# Smart_Humidifier.net
KiCad netlist of a schematic drawn in Altium Designer
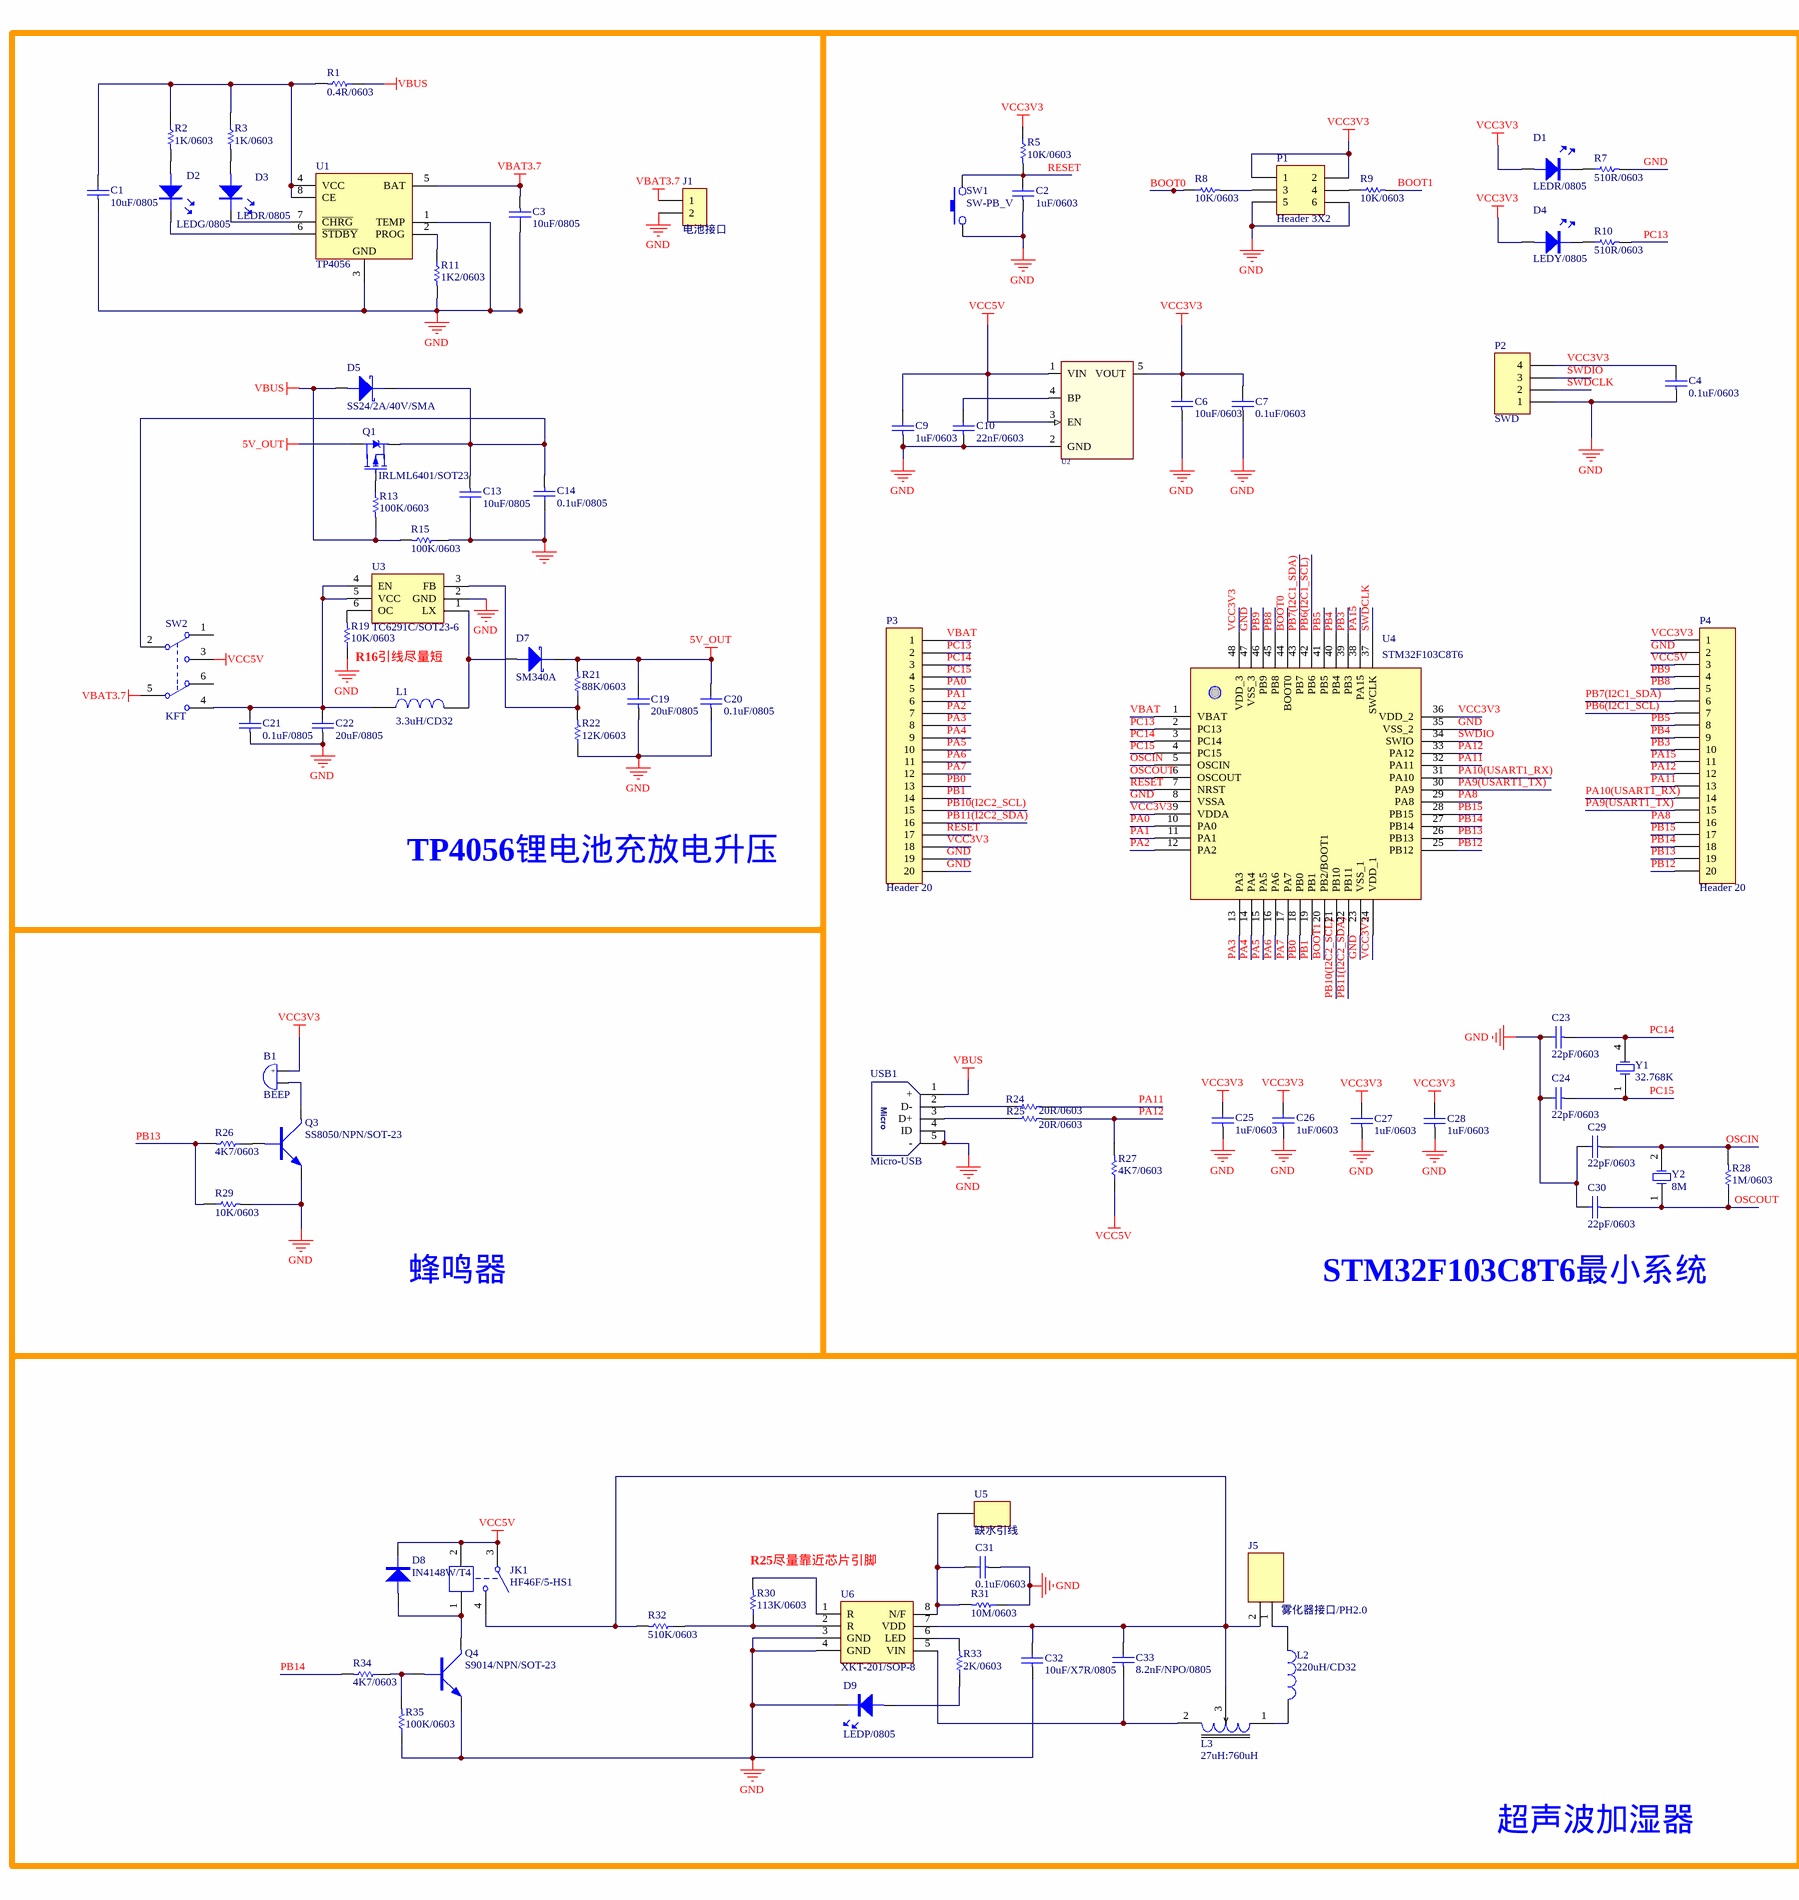
[diagram p0: Smart Humidifier.SchDoc, left]
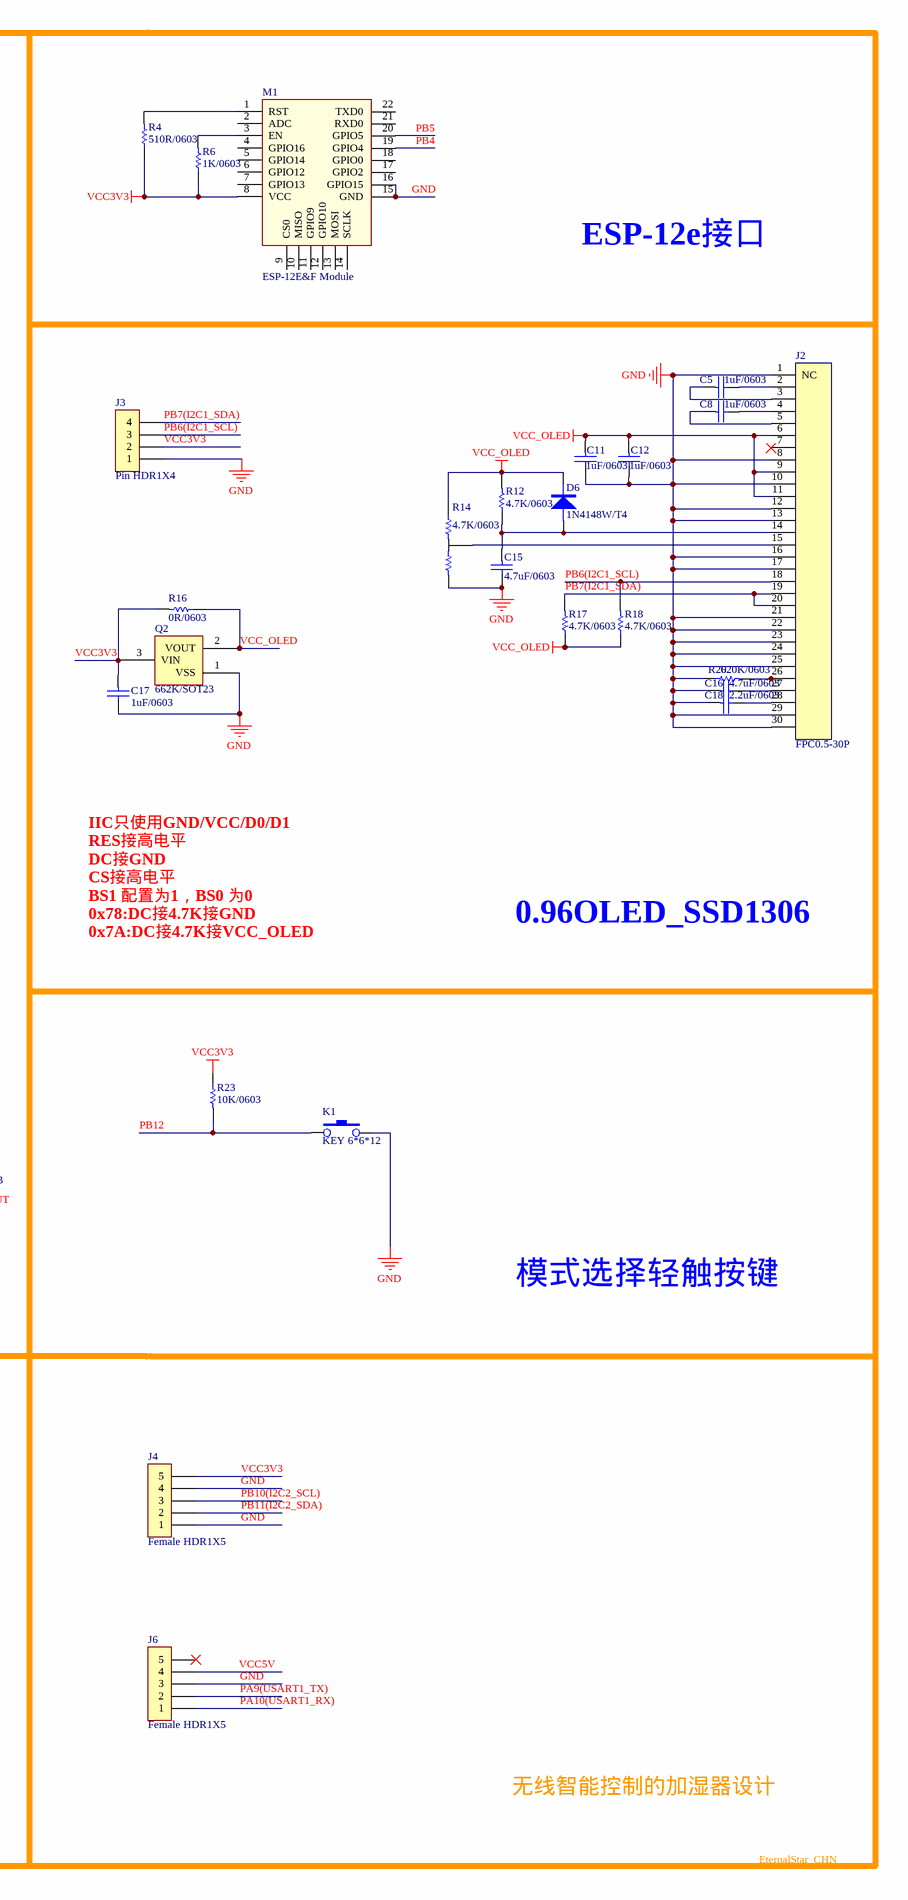
[diagram p1: Smart Humidifier.SchDoc, right]

(export (version "E")
  (design (tool "Eeschema 10.0.6"))
  (components
    (comp (ref "B1")
      (value "BEEP")
      (footprint "BEEP 5x9x5.5")
      (description "蜂鸣器")
      (libsource (lib "蜂鸣器") (part "BEEP"))
    )
    (comp (ref "C1")
      (value "10uF/0805")
      (footprint "0805C")
      (description "无极性电容")
      (libsource (lib "电容") (part "CAP"))
    )
    (comp (ref "C2")
      (value "1uF/0603")
      (footprint "0603C")
      (description "无极性电容")
      (libsource (lib "电容") (part "CAP"))
    )
    (comp (ref "C3")
      (value "10uF/0805")
      (footprint "0805C")
      (description "无极性电容")
      (libsource (lib "电容") (part "CAP"))
    )
    (comp (ref "C4")
      (value "0.1uF/0603")
      (footprint "0603C")
      (description "无极性电容")
      (libsource (lib "电容") (part "CAP"))
    )
    (comp (ref "C5")
      (value "1uF/0603")
      (footprint "0603C")
      (description "无极性电容")
      (libsource (lib "电容") (part "CAP"))
    )
    (comp (ref "C6")
      (value "10uF/0603")
      (footprint "0603C")
      (description "无极性电容")
      (libsource (lib "电容") (part "CAP"))
    )
    (comp (ref "C7")
      (value "0.1uF/0603")
      (footprint "0603C")
      (description "无极性电容")
      (libsource (lib "电容") (part "CAP"))
    )
    (comp (ref "C8")
      (value "1uF/0603")
      (footprint "0603C")
      (description "无极性电容")
      (libsource (lib "电容") (part "CAP"))
    )
    (comp (ref "C9")
      (value "1uF/0603")
      (footprint "0603C")
      (description "无极性电容")
      (libsource (lib "电容") (part "CAP"))
    )
    (comp (ref "C10")
      (value "22nF/0603")
      (footprint "0603C")
      (description "无极性电容")
      (libsource (lib "电容") (part "CAP"))
    )
    (comp (ref "C11")
      (value "1uF/0603")
      (footprint "0603C")
      (description "无极性电容")
      (libsource (lib "电容") (part "CAP"))
    )
    (comp (ref "C12")
      (value "1uF/0603")
      (footprint "0603C")
      (description "无极性电容")
      (libsource (lib "电容") (part "CAP"))
    )
    (comp (ref "C13")
      (value "10uF/0805")
      (footprint "0805C")
      (description "无极性电容")
      (libsource (lib "电容") (part "CAP"))
    )
    (comp (ref "C14")
      (value "0.1uF/0805")
      (footprint "0805C")
      (description "无极性电容")
      (libsource (lib "电容") (part "CAP"))
    )
    (comp (ref "C15")
      (value "4.7uF/0603")
      (footprint "0603C")
      (description "无极性电容")
      (libsource (lib "电容") (part "CAP"))
    )
    (comp (ref "C16")
      (value "4.7uF/0603")
      (footprint "0603C")
      (description "无极性电容")
      (libsource (lib "电容") (part "CAP"))
    )
    (comp (ref "C17")
      (value "1uF/0603")
      (footprint "0603C")
      (description "无极性电容")
      (libsource (lib "电容") (part "CAP"))
    )
    (comp (ref "C18")
      (value "2.2uF/0603")
      (footprint "0603C")
      (description "无极性电容")
      (libsource (lib "电容") (part "CAP"))
    )
    (comp (ref "C19")
      (value "20uF/0805")
      (footprint "0805C")
      (description "无极性电容")
      (libsource (lib "电容") (part "CAP"))
    )
    (comp (ref "C20")
      (value "0.1uF/0805")
      (footprint "0805C")
      (description "无极性电容")
      (libsource (lib "电容") (part "CAP"))
    )
    (comp (ref "C21")
      (value "0.1uF/0805")
      (footprint "0805C")
      (description "无极性电容")
      (libsource (lib "电容") (part "CAP"))
    )
    (comp (ref "C22")
      (value "20uF/0805")
      (footprint "0805C")
      (description "无极性电容")
      (libsource (lib "电容") (part "CAP"))
    )
    (comp (ref "C23")
      (value "22pF/0603")
      (footprint "0603C")
      (description "无极性电容")
      (libsource (lib "电容") (part "CAP"))
    )
    (comp (ref "C24")
      (value "22pF/0603")
      (footprint "0603C")
      (description "无极性电容")
      (libsource (lib "电容") (part "CAP"))
    )
    (comp (ref "C25")
      (value "1uF/0603")
      (footprint "0603C")
      (description "无极性电容")
      (libsource (lib "电容") (part "CAP"))
    )
    (comp (ref "C26")
      (value "1uF/0603")
      (footprint "0603C")
      (description "无极性电容")
      (libsource (lib "电容") (part "CAP"))
    )
    (comp (ref "C27")
      (value "1uF/0603")
      (footprint "0603C")
      (description "无极性电容")
      (libsource (lib "电容") (part "CAP"))
    )
    (comp (ref "C28")
      (value "1uF/0603")
      (footprint "0603C")
      (description "无极性电容")
      (libsource (lib "电容") (part "CAP"))
    )
    (comp (ref "C29")
      (value "22pF/0603")
      (footprint "0603C")
      (description "无极性电容")
      (libsource (lib "电容") (part "CAP"))
    )
    (comp (ref "C30")
      (value "22pF/0603")
      (footprint "0603C")
      (description "无极性电容")
      (libsource (lib "电容") (part "CAP"))
    )
    (comp (ref "C31")
      (value "0.1uF/0603")
      (footprint "0603C")
      (description "无极性电容")
      (libsource (lib "") (part "CAP_1"))
    )
    (comp (ref "C32")
      (value "10uF/X7R/0805")
      (footprint "0805C")
      (description "无极性电容")
      (libsource (lib "电容") (part "CAP"))
    )
    (comp (ref "C33")
      (value "8.2nF/NPO/0805")
      (footprint "0805C")
      (description "无极性电容")
      (libsource (lib "电容") (part "CAP"))
    )
    (comp (ref "D1") (value "LEDR/0805") (footprint "LED-0805R") (libsource (lib "LED") (part "LED")))
    (comp (ref "D2") (value "LEDG/0805") (footprint "LED-0805G") (libsource (lib "LED") (part "LED")))
    (comp (ref "D3") (value "LEDR/0805") (footprint "LED-0805R") (libsource (lib "LED") (part "LED")))
    (comp (ref "D4") (value "LEDY/0805") (footprint "LED-0805Y") (libsource (lib "LED") (part "LED")))
    (comp (ref "D5")
      (value "SS24/2A/40V/SMA")
      (footprint "SMA/DO-214AC")
      (description "肖特基二极管")
      (libsource (lib "二极管") (part "DIODE SCHOTTKY"))
    )
    (comp (ref "D6")
      (value "1N4148W/T4")
      (footprint "SOD-123")
      (description "普通二极管")
      (libsource (lib "二极管") (part "DIODE"))
    )
    (comp (ref "D7")
      (value "SM340A")
      (footprint "SMA/DO-214AC")
      (description "肖特基二极管")
      (libsource (lib "二极管") (part "DIODE SCHOTTKY"))
    )
    (comp (ref "D8")
      (value "IN4148W/T4")
      (footprint "SOD-123")
      (description "普通二极管")
      (libsource (lib "二极管") (part "DIODE"))
    )
    (comp (ref "D9") (value "LEDP/0805") (footprint "LED-0805Y") (libsource (lib "LED") (part "LED")))
    (comp (ref "J1")
      (value "电池接口")
      (footprint "Fe-HDR1X2/2.54-S")
      (libsource (lib "排母") (part "Female HDR1X2"))
    )
    (comp (ref "J2")
      (value "FPC0.5-30P")
      (footprint "FPC0.5-30P")
      (description "贴片")
      (libsource (lib "FPC") (part "FPC0.5-30P"))
    )
    (comp (ref "J3")
      (value "Pin HDR1X4")
      (footprint "Pin HDR1X4/2.54mm-S")
      (libsource (lib "排针") (part "Pin HDR1X4"))
    )
    (comp (ref "J4")
      (value "Female HDR1X5")
      (footprint "Fe-HDR1X5/2.54-S")
      (libsource (lib "排母") (part "Female HDR1X5"))
    )
    (comp (ref "J5") (value "雾化器接口/PH2.0") (footprint "PH2.0-2P") (libsource (lib "PH") (part "PH2.0-2P")))
    (comp (ref "J6")
      (value "Female HDR1X5")
      (footprint "Fe-HDR1X5/2.54-S")
      (libsource (lib "排母") (part "Female HDR1X5"))
    )
    (comp (ref "JK1")
      (value "HF46F/5-HS1")
      (footprint "HF46-xx-HS1")
      (description "5V一组常开")
      (libsource (lib "继电器") (part "HF46F/5-HS1"))
    )
    (comp (ref "K1") (value "KEY 6*6*12") (footprint "DIP-6X6X12_C") (libsource (lib "轻触开关") (part "KEY")))
    (comp (ref "L1")
      (value "3.3uH/CD32")
      (footprint "CD32")
      (description "INDUCTOR")
      (libsource (lib "电感") (part "INDUCTOR"))
    )
    (comp (ref "L2")
      (value "220uH/CD32")
      (footprint "CD32")
      (description "INDUCTOR")
      (libsource (lib "Smart Humidifier") (part "INDUCTOR"))
    )
    (comp (ref "L3")
      (value "27uH:760uH")
      (footprint "INDUCTOR Tripod")
      (description "三脚工字形电感线圈直插式")
      (libsource (lib "Smart Humidifier") (part "INDUCTOR Tripod"))
    )
    (comp (ref "M1")
      (value "ESP-12E&F Module")
      (footprint "ESP-12E&F Module")
      (libsource (lib "ESP模块") (part "ESP-12E&F Module"))
    )
    (comp (ref "P1")
      (value "Header 3X2")
      (footprint "HDR-3X2")
      (description "Header, 3-Pin, Dual row")
      (libsource (lib "STM32F103C8T6") (part "Header 3X2"))
    )
    (comp (ref "P2")
      (value "SWD")
      (footprint "HDR-1X4_H")
      (description "Header, 4-Pin")
      (libsource (lib "STM32F103C8T6") (part "Header 4"))
    )
    (comp (ref "P3")
      (value "Header 20")
      (footprint "HDR1X20")
      (description "Header, 20-Pin")
      (libsource (lib "STM32F103C8T6") (part "Header 20"))
    )
    (comp (ref "P4")
      (value "Header 20")
      (footprint "HDR1X20")
      (description "Header, 20-Pin")
      (libsource (lib "") (part "Header 20_1"))
    )
    (comp (ref "Q1")
      (value "IRLML6401/SOT23")
      (footprint "SOT23")
      (description "P沟道场效应管")
      (libsource (lib "MOS管") (part "P-MOS"))
    )
    (comp (ref "Q2")
      (value "662K/SOT23")
      (footprint "SOT23")
      (description "SOT23封装LDO")
      (libsource (lib "电源芯片") (part "LDO_SOT23"))
    )
    (comp (ref "Q3")
      (value "SS8050/NPN/SOT-23")
      (footprint "SOT-23")
      (description "NPN三极管")
      (libsource (lib "三极管") (part "NPN"))
    )
    (comp (ref "Q4")
      (value "S9014/NPN/SOT-23")
      (footprint "SOT-23")
      (description "NPN三极管")
      (libsource (lib "三极管") (part "NPN"))
    )
    (comp (ref "R1") (value "0.4R/0603") (footprint "0603R") (libsource (lib "电阻") (part "RES")))
    (comp (ref "R2") (value "1K/0603") (footprint "0603R") (libsource (lib "电阻") (part "RES")))
    (comp (ref "R3") (value "1K/0603") (footprint "0603R") (libsource (lib "电阻") (part "RES")))
    (comp (ref "R4") (value "510R/0603") (footprint "0603R") (libsource (lib "电阻") (part "RES")))
    (comp (ref "R5") (value "10K/0603") (footprint "0603R") (libsource (lib "电阻") (part "RES")))
    (comp (ref "R6") (value "1K/0603") (footprint "0603R") (libsource (lib "电阻") (part "RES")))
    (comp (ref "R7") (value "510R/0603") (footprint "0603R") (libsource (lib "电阻") (part "RES")))
    (comp (ref "R8") (value "10K/0603") (footprint "0603R") (libsource (lib "电阻") (part "RES")))
    (comp (ref "R9") (value "10K/0603") (footprint "0603R") (libsource (lib "电阻") (part "RES")))
    (comp (ref "R10") (value "510R/0603") (footprint "0603R") (libsource (lib "电阻") (part "RES")))
    (comp (ref "R11") (value "1K2/0603") (footprint "0603R") (libsource (lib "电阻") (part "RES")))
    (comp (ref "R12") (value "4.7K/0603") (footprint "0603R") (libsource (lib "电阻") (part "RES")))
    (comp (ref "R13") (value "100K/0603") (footprint "0603R") (libsource (lib "电阻") (part "RES")))
    (comp (ref "R14") (value "4.7K/0603") (footprint "SW_0603R") (libsource (lib "电阻") (part "RES_SW")))
    (comp (ref "R15") (value "100K/0603") (footprint "0603R") (libsource (lib "电阻") (part "RES")))
    (comp (ref "R16") (value "0R/0603") (footprint "0603R") (libsource (lib "电阻") (part "RES")))
    (comp (ref "R17") (value "4.7K/0603") (footprint "0603R") (libsource (lib "电阻") (part "RES")))
    (comp (ref "R18") (value "4.7K/0603") (footprint "0603R") (libsource (lib "电阻") (part "RES")))
    (comp (ref "R19") (value "10K/0603") (footprint "0603R") (libsource (lib "电阻") (part "RES")))
    (comp (ref "R20") (value "620K/0603") (footprint "0603R") (libsource (lib "电阻") (part "RES")))
    (comp (ref "R21") (value "88K/0603") (footprint "0603R") (libsource (lib "电阻") (part "RES")))
    (comp (ref "R22") (value "12K/0603") (footprint "0603R") (libsource (lib "电阻") (part "RES")))
    (comp (ref "R23") (value "10K/0603") (footprint "0603R") (libsource (lib "电阻") (part "RES")))
    (comp (ref "R24") (value "20R/0603") (footprint "0603R") (libsource (lib "电阻") (part "RES")))
    (comp (ref "R25") (value "20R/0603") (footprint "0603R") (libsource (lib "电阻") (part "RES")))
    (comp (ref "R26") (value "4K7/0603") (footprint "0603R") (libsource (lib "电阻") (part "RES")))
    (comp (ref "R27") (value "4K7/0603") (footprint "0603R") (libsource (lib "电阻") (part "RES")))
    (comp (ref "R28") (value "1M/0603") (footprint "0603R") (libsource (lib "电阻") (part "RES")))
    (comp (ref "R29") (value "10K/0603") (footprint "0603R") (libsource (lib "电阻") (part "RES")))
    (comp (ref "R30") (value "113K/0603") (footprint "0603R") (libsource (lib "电阻") (part "RES")))
    (comp (ref "R31") (value "10M/0603") (footprint "0603R") (libsource (lib "电阻") (part "RES")))
    (comp (ref "R32") (value "510K/0603") (footprint "0603R") (libsource (lib "电阻") (part "RES")))
    (comp (ref "R33") (value "2K/0603") (footprint "0603R") (libsource (lib "电阻") (part "RES")))
    (comp (ref "R34") (value "4K7/0603") (footprint "0603R") (libsource (lib "电阻") (part "RES")))
    (comp (ref "R35") (value "100K/0603") (footprint "0603R") (libsource (lib "电阻") (part "RES")))
    (comp (ref "SW1")
      (value "SW-PB_V")
      (footprint "TSW SMD-3*6*2.5")
      (description "SWITCH")
      (libsource (lib "STM32F103C8T6") (part "SW-PB_V"))
    )
    (comp (ref "SW2")
      (value "KFT")
      (footprint "KFT DIP-7X7")
      (description "Self-locking Switch")
      (libsource (lib "Smart Humidifier") (part "KFT_7X7-DIP"))
    )
    (comp (ref "U1") (value "TP4056") (footprint "SOP8") (libsource (lib "电源芯片") (part "TP4056")))
    (comp (ref "U2")
      (value "RT9193")
      (footprint "SOT23-5L")
      (fields (field (name "ICA_PARTNUM") "$$2191094$$RT9193-15CU5") (field (name "PART NUMBER") "TMP-13"))
      (libsource (lib "STM32F103C8T6") (part "RT9193X_5P"))
    )
    (comp (ref "U3")
      (value "TC6291C/SOT23-6")
      (footprint "SOT23-6")
      (description "DC-DC升压IC")
      (libsource (lib "Li_Test") (part "TC6291C"))
    )
    (comp (ref "U4")
      (value "STM32F103C8T6")
      (footprint "TQFP48 7x7_L")
      (libsource (lib "STM32F103C8T6") (part "STM32F103C8T6"))
    )
    (comp (ref "U5") (value "缺水引线") (footprint "通孔焊盘") (libsource (lib "Smart Humidifier") (part "过孔焊盘")))
    (comp (ref "U6")
      (value "XKT-201/SOP-8")
      (footprint "SOP8")
      (description "5V加湿器驱动芯片")
      (libsource (lib "Smart Humidifier") (part "XKT-201"))
    )
    (comp (ref "USB1")
      (value "Micro-USB")
      (footprint "USB-micro_B")
      (libsource (lib "USB") (part "Micro-USB"))
    )
    (comp (ref "Y1")
      (value "32.768K")
      (footprint "MC-306")
      (description "Crystal Oscillator")
      (libsource (lib "STM32F103C8T6") (part "XTAL"))
    )
    (comp (ref "Y2")
      (value "8M")
      (footprint "XTAL-49S DIP")
      (description "Crystal Oscillator")
      (libsource (lib "") (part "XTAL_1"))
    )
  )
  (nets
    (net (code "1") (name "/BOOT0") (class "Default")
      (node (ref "R8") (pin "1") (pinfunction "1_1") (pintype "passive"))
      (node (ref "U4") (pin "44") (pinfunction "BOOT0_44") (pintype "passive"))
    )
    (net (code "2") (name "/BOOT1") (class "Default")
      (node (ref "R9") (pin "2") (pinfunction "2_2") (pintype "passive"))
      (node (ref "U4") (pin "20") (pinfunction "PB2/BOOT1_20") (pintype "passive"))
    )
    (net (code "3") (name "/OSCIN") (class "Default")
      (node (ref "C29") (pin "1") (pinfunction "1_1") (pintype "passive"))
      (node (ref "R28") (pin "2") (pinfunction "2_2") (pintype "passive"))
      (node (ref "U4") (pin "5") (pinfunction "OSCIN_5") (pintype "passive"))
      (node (ref "Y2") (pin "2") (pinfunction "OSC2_2") (pintype "passive"))
    )
    (net (code "4") (name "/OSCOUT") (class "Default")
      (node (ref "C30") (pin "1") (pinfunction "1_1") (pintype "passive"))
      (node (ref "R28") (pin "1") (pinfunction "1_1") (pintype "passive"))
      (node (ref "U4") (pin "6") (pinfunction "OSCOUT_6") (pintype "passive"))
      (node (ref "Y2") (pin "1") (pinfunction "OSC1_1") (pintype "passive"))
    )
    (net (code "5") (name "/PA0") (class "Default")
      (node (ref "P3") (pin "5") (pinfunction "5_5") (pintype "passive"))
      (node (ref "U4") (pin "10") (pinfunction "PA0_10") (pintype "passive"))
    )
    (net (code "6") (name "/PA1") (class "Default")
      (node (ref "P3") (pin "6") (pinfunction "6_6") (pintype "passive"))
      (node (ref "U4") (pin "11") (pinfunction "PA1_11") (pintype "passive"))
    )
    (net (code "7") (name "/PA2") (class "Default")
      (node (ref "P3") (pin "7") (pinfunction "7_7") (pintype "passive"))
      (node (ref "U4") (pin "12") (pinfunction "PA2_12") (pintype "passive"))
    )
    (net (code "8") (name "/PA3") (class "Default")
      (node (ref "P3") (pin "8") (pinfunction "8_8") (pintype "passive"))
      (node (ref "U4") (pin "13") (pinfunction "PA3_13") (pintype "passive"))
    )
    (net (code "9") (name "/PA4") (class "Default")
      (node (ref "P3") (pin "9") (pinfunction "9_9") (pintype "passive"))
      (node (ref "U4") (pin "14") (pinfunction "PA4_14") (pintype "passive"))
    )
    (net (code "10") (name "/PA5") (class "Default")
      (node (ref "P3") (pin "10") (pinfunction "10_10") (pintype "passive"))
      (node (ref "U4") (pin "15") (pinfunction "PA5_15") (pintype "passive"))
    )
    (net (code "11") (name "/PA6") (class "Default")
      (node (ref "P3") (pin "11") (pinfunction "11_11") (pintype "passive"))
      (node (ref "U4") (pin "16") (pinfunction "PA6_16") (pintype "passive"))
    )
    (net (code "12") (name "/PA7") (class "Default")
      (node (ref "P3") (pin "12") (pinfunction "12_12") (pintype "passive"))
      (node (ref "U4") (pin "17") (pinfunction "PA7_17") (pintype "passive"))
    )
    (net (code "13") (name "/PA8") (class "Default")
      (node (ref "P4") (pin "16") (pinfunction "16_16") (pintype "passive"))
      (node (ref "U4") (pin "29") (pinfunction "PA8_29") (pintype "passive"))
    )
    (net (code "14") (name "/PA9(USART1_TX)") (class "Default")
      (node (ref "J6") (pin "2") (pinfunction "2_2") (pintype "passive"))
      (node (ref "P4") (pin "15") (pinfunction "15_15") (pintype "passive"))
      (node (ref "U4") (pin "30") (pinfunction "PA9_30") (pintype "passive"))
    )
    (net (code "15") (name "/PA10(USART1_RX)") (class "Default")
      (node (ref "J6") (pin "1") (pinfunction "1_1") (pintype "passive"))
      (node (ref "P4") (pin "14") (pinfunction "14_14") (pintype "passive"))
      (node (ref "U4") (pin "31") (pinfunction "PA10_31") (pintype "passive"))
    )
    (net (code "16") (name "/PA11") (class "Default")
      (node (ref "P4") (pin "13") (pinfunction "13_13") (pintype "passive"))
      (node (ref "R24") (pin "2") (pinfunction "2_2") (pintype "passive"))
      (node (ref "U4") (pin "32") (pinfunction "PA11_32") (pintype "passive"))
    )
    (net (code "17") (name "/PA12") (class "Default")
      (node (ref "P4") (pin "12") (pinfunction "12_12") (pintype "passive"))
      (node (ref "R25") (pin "2") (pinfunction "2_2") (pintype "passive"))
      (node (ref "R27") (pin "2") (pinfunction "2_2") (pintype "passive"))
      (node (ref "U4") (pin "33") (pinfunction "PA12_33") (pintype "passive"))
    )
    (net (code "18") (name "/PA15") (class "Default")
      (node (ref "P4") (pin "11") (pinfunction "11_11") (pintype "passive"))
      (node (ref "U4") (pin "38") (pinfunction "PA15_38") (pintype "passive"))
    )
    (net (code "19") (name "/PB0") (class "Default")
      (node (ref "P3") (pin "13") (pinfunction "13_13") (pintype "passive"))
      (node (ref "U4") (pin "18") (pinfunction "PB0_18") (pintype "passive"))
    )
    (net (code "20") (name "/PB1") (class "Default")
      (node (ref "P3") (pin "14") (pinfunction "14_14") (pintype "passive"))
      (node (ref "U4") (pin "19") (pinfunction "PB1_19") (pintype "passive"))
    )
    (net (code "21") (name "/PB3") (class "Default")
      (node (ref "P4") (pin "10") (pinfunction "10_10") (pintype "passive"))
      (node (ref "U4") (pin "39") (pinfunction "PB3_39") (pintype "passive"))
    )
    (net (code "22") (name "/PB4") (class "Default")
      (node (ref "M1") (pin "19") (pinfunction "GPIO4_19") (pintype "passive"))
      (node (ref "P4") (pin "9") (pinfunction "9_9") (pintype "passive"))
      (node (ref "U4") (pin "40") (pinfunction "PB4_40") (pintype "passive"))
    )
    (net (code "23") (name "/PB5") (class "Default")
      (node (ref "M1") (pin "20") (pinfunction "GPIO5_20") (pintype "passive"))
      (node (ref "P4") (pin "8") (pinfunction "8_8") (pintype "passive"))
      (node (ref "U4") (pin "41") (pinfunction "PB5_41") (pintype "passive"))
    )
    (net (code "24") (name "/PB6(I2C1_SCL)") (class "Default")
      (node (ref "J2") (pin "18") (pinfunction "D0_18") (pintype "passive"))
      (node (ref "J3") (pin "3") (pinfunction "3_3") (pintype "passive"))
      (node (ref "P4") (pin "7") (pinfunction "7_7") (pintype "passive"))
      (node (ref "R18") (pin "2") (pinfunction "2_2") (pintype "passive"))
      (node (ref "U4") (pin "42") (pinfunction "PB6_42") (pintype "passive"))
    )
    (net (code "25") (name "/PB7(I2C1_SDA)") (class "Default")
      (node (ref "J2") (pin "19") (pinfunction "D1_19") (pintype "passive"))
      (node (ref "J2") (pin "20") (pinfunction "D2_20") (pintype "passive"))
      (node (ref "J3") (pin "4") (pinfunction "4_4") (pintype "passive"))
      (node (ref "P4") (pin "6") (pinfunction "6_6") (pintype "passive"))
      (node (ref "R17") (pin "2") (pinfunction "2_2") (pintype "passive"))
      (node (ref "U4") (pin "43") (pinfunction "PB7_43") (pintype "passive"))
    )
    (net (code "26") (name "/PB8") (class "Default")
      (node (ref "P4") (pin "5") (pinfunction "5_5") (pintype "passive"))
      (node (ref "U4") (pin "45") (pinfunction "PB8_45") (pintype "passive"))
    )
    (net (code "27") (name "/PB9") (class "Default")
      (node (ref "P4") (pin "4") (pinfunction "4_4") (pintype "passive"))
      (node (ref "U4") (pin "46") (pinfunction "PB9_46") (pintype "passive"))
    )
    (net (code "28") (name "/PB10(I2C2_SCL)") (class "Default")
      (node (ref "J4") (pin "3") (pinfunction "3_3") (pintype "passive"))
      (node (ref "P3") (pin "15") (pinfunction "15_15") (pintype "passive"))
      (node (ref "U4") (pin "21") (pinfunction "PB10_21") (pintype "passive"))
    )
    (net (code "29") (name "/PB11(I2C2_SDA)") (class "Default")
      (node (ref "J4") (pin "2") (pinfunction "2_2") (pintype "passive"))
      (node (ref "P3") (pin "16") (pinfunction "16_16") (pintype "passive"))
      (node (ref "U4") (pin "22") (pinfunction "PB11_22") (pintype "passive"))
    )
    (net (code "30") (name "/PB12") (class "Default")
      (node (ref "K1") (pin "1") (pinfunction "1_1") (pintype "passive"))
      (node (ref "P4") (pin "20") (pinfunction "20_20") (pintype "passive"))
      (node (ref "R23") (pin "2") (pinfunction "2_2") (pintype "passive"))
      (node (ref "U4") (pin "25") (pinfunction "PB12_25") (pintype "passive"))
    )
    (net (code "31") (name "/PB13") (class "Default")
      (node (ref "P4") (pin "19") (pinfunction "19_19") (pintype "passive"))
      (node (ref "R26") (pin "2") (pinfunction "2_2") (pintype "passive"))
      (node (ref "R29") (pin "1") (pinfunction "1_1") (pintype "passive"))
      (node (ref "U4") (pin "26") (pinfunction "PB13_26") (pintype "passive"))
    )
    (net (code "32") (name "/PB14") (class "Default")
      (node (ref "P4") (pin "18") (pinfunction "18_18") (pintype "passive"))
      (node (ref "R34") (pin "2") (pinfunction "2_2") (pintype "passive"))
      (node (ref "U4") (pin "27") (pinfunction "PB14_27") (pintype "passive"))
    )
    (net (code "33") (name "/PB15") (class "Default")
      (node (ref "P4") (pin "17") (pinfunction "17_17") (pintype "passive"))
      (node (ref "U4") (pin "28") (pinfunction "PB15_28") (pintype "passive"))
    )
    (net (code "34") (name "/PC13") (class "Default")
      (node (ref "P3") (pin "2") (pinfunction "2_2") (pintype "passive"))
      (node (ref "R10") (pin "2") (pinfunction "2_2") (pintype "passive"))
      (node (ref "U4") (pin "2") (pinfunction "PC13_2") (pintype "passive"))
    )
    (net (code "35") (name "/PC14") (class "Default")
      (node (ref "C23") (pin "1") (pinfunction "1_1") (pintype "passive"))
      (node (ref "P3") (pin "3") (pinfunction "3_3") (pintype "passive"))
      (node (ref "U4") (pin "3") (pinfunction "PC14_3") (pintype "passive"))
      (node (ref "Y1") (pin "4") (pinfunction "OSC2_4") (pintype "passive"))
    )
    (net (code "36") (name "/PC15") (class "Default")
      (node (ref "C24") (pin "1") (pinfunction "1_1") (pintype "passive"))
      (node (ref "P3") (pin "4") (pinfunction "4_4") (pintype "passive"))
      (node (ref "U4") (pin "4") (pinfunction "PC15_4") (pintype "passive"))
      (node (ref "Y1") (pin "1") (pinfunction "OSC1_1") (pintype "passive"))
    )
    (net (code "37") (name "/RESET") (class "Default")
      (node (ref "C2") (pin "2") (pinfunction "2_2") (pintype "passive"))
      (node (ref "P3") (pin "17") (pinfunction "17_17") (pintype "passive"))
      (node (ref "R5") (pin "2") (pinfunction "2_2") (pintype "passive"))
      (node (ref "SW1") (pin "2") (pinfunction "2_2") (pintype "passive"))
      (node (ref "U4") (pin "7") (pinfunction "NRST_7") (pintype "passive"))
    )
    (net (code "38") (name "/SWDCLK") (class "Default")
      (node (ref "P2") (pin "2") (pinfunction "2_2") (pintype "passive"))
      (node (ref "U4") (pin "37") (pinfunction "SWCLK_37") (pintype "passive"))
    )
    (net (code "39") (name "/SWDIO") (class "Default")
      (node (ref "P2") (pin "3") (pinfunction "3_3") (pintype "passive"))
      (node (ref "U4") (pin "34") (pinfunction "SWIO_34") (pintype "passive"))
    )
    (net (code "40") (name "/VBAT") (class "Default")
      (node (ref "P3") (pin "1") (pinfunction "1_1") (pintype "passive"))
      (node (ref "U4") (pin "1") (pinfunction "VBAT_1") (pintype "passive"))
    )
    (net (code "41") (name "5V_OUT") (class "Default")
      (node (ref "C19") (pin "2") (pinfunction "2_2") (pintype "passive"))
      (node (ref "C20") (pin "2") (pinfunction "2_2") (pintype "passive"))
      (node (ref "D7") (pin "K") (pinfunction "K_K") (pintype "passive"))
      (node (ref "Q1") (pin "D") (pinfunction "D_D") (pintype "passive"))
      (node (ref "R21") (pin "2") (pinfunction "2_2") (pintype "passive"))
    )
    (net (code "42") (name "GND") (class "Default")
      (node (ref "C1") (pin "1") (pinfunction "1_1") (pintype "passive"))
      (node (ref "C10") (pin "1") (pinfunction "1_1") (pintype "passive"))
      (node (ref "C11") (pin "2") (pinfunction "2_2") (pintype "passive"))
      (node (ref "C12") (pin "2") (pinfunction "2_2") (pintype "passive"))
      (node (ref "C13") (pin "2") (pinfunction "2_2") (pintype "passive"))
      (node (ref "C14") (pin "2") (pinfunction "2_2") (pintype "passive"))
      (node (ref "C15") (pin "2") (pinfunction "2_2") (pintype "passive"))
      (node (ref "C16") (pin "1") (pinfunction "1_1") (pintype "passive"))
      (node (ref "C17") (pin "2") (pinfunction "2_2") (pintype "passive"))
      (node (ref "C18") (pin "1") (pinfunction "1_1") (pintype "passive"))
      (node (ref "C19") (pin "1") (pinfunction "1_1") (pintype "passive"))
      (node (ref "C2") (pin "1") (pinfunction "1_1") (pintype "passive"))
      (node (ref "C20") (pin "1") (pinfunction "1_1") (pintype "passive"))
      (node (ref "C21") (pin "1") (pinfunction "1_1") (pintype "passive"))
      (node (ref "C22") (pin "1") (pinfunction "1_1") (pintype "passive"))
      (node (ref "C23") (pin "2") (pinfunction "2_2") (pintype "passive"))
      (node (ref "C24") (pin "2") (pinfunction "2_2") (pintype "passive"))
      (node (ref "C25") (pin "1") (pinfunction "1_1") (pintype "passive"))
      (node (ref "C26") (pin "1") (pinfunction "1_1") (pintype "passive"))
      (node (ref "C27") (pin "1") (pinfunction "1_1") (pintype "passive"))
      (node (ref "C28") (pin "1") (pinfunction "1_1") (pintype "passive"))
      (node (ref "C29") (pin "2") (pinfunction "2_2") (pintype "passive"))
      (node (ref "C3") (pin "2") (pinfunction "2_2") (pintype "passive"))
      (node (ref "C30") (pin "2") (pinfunction "2_2") (pintype "passive"))
      (node (ref "C31") (pin "2") (pinfunction "2_2") (pintype "passive"))
      (node (ref "C32") (pin "1") (pinfunction "1_1") (pintype "passive"))
      (node (ref "C4") (pin "1") (pinfunction "1_1") (pintype "passive"))
      (node (ref "C6") (pin "1") (pinfunction "1_1") (pintype "passive"))
      (node (ref "C7") (pin "1") (pinfunction "1_1") (pintype "passive"))
      (node (ref "C9") (pin "1") (pinfunction "1_1") (pintype "passive"))
      (node (ref "D9") (pin "K") (pinfunction "K_K") (pintype "passive"))
      (node (ref "J1") (pin "2") (pinfunction "2_2") (pintype "passive"))
      (node (ref "J2") (pin "1") (pinfunction "NC_1") (pintype "passive"))
      (node (ref "J2") (pin "10") (pinfunction "BS0_10") (pintype "passive"))
      (node (ref "J2") (pin "12") (pinfunction "NC_12") (pintype "passive"))
      (node (ref "J2") (pin "13") (pinfunction "CS_13") (pintype "passive"))
      (node (ref "J2") (pin "16") (pinfunction "E/RD_16") (pintype "passive"))
      (node (ref "J2") (pin "17") (pinfunction "R/W_17") (pintype "passive"))
      (node (ref "J2") (pin "21") (pinfunction "D3_21") (pintype "passive"))
      (node (ref "J2") (pin "22") (pinfunction "D4_22") (pintype "passive"))
      (node (ref "J2") (pin "23") (pinfunction "D5_23") (pintype "passive"))
      (node (ref "J2") (pin "24") (pinfunction "D6_24") (pintype "passive"))
      (node (ref "J2") (pin "25") (pinfunction "D7_25") (pintype "passive"))
      (node (ref "J2") (pin "29") (pinfunction "VLSS_29") (pintype "passive"))
      (node (ref "J2") (pin "30") (pinfunction "NC_30") (pintype "passive"))
      (node (ref "J2") (pin "8") (pinfunction "VSS_8") (pintype "passive"))
      (node (ref "J3") (pin "1") (pinfunction "1_1") (pintype "passive"))
      (node (ref "J4") (pin "1") (pinfunction "1_1") (pintype "passive"))
      (node (ref "J4") (pin "4") (pinfunction "4_4") (pintype "passive"))
      (node (ref "J6") (pin "3") (pinfunction "3_3") (pintype "passive"))
      (node (ref "K1") (pin "3") (pinfunction "3_3") (pintype "passive"))
      (node (ref "M1") (pin "15") (pinfunction "GND_15") (pintype "passive"))
      (node (ref "M1") (pin "16") (pinfunction "GPIO15_16") (pintype "passive"))
      (node (ref "P1") (pin "5") (pinfunction "5_5") (pintype "passive"))
      (node (ref "P1") (pin "6") (pinfunction "6_6") (pintype "passive"))
      (node (ref "P2") (pin "1") (pinfunction "1_1") (pintype "passive"))
      (node (ref "P3") (pin "19") (pinfunction "19_19") (pintype "passive"))
      (node (ref "P3") (pin "20") (pinfunction "20_20") (pintype "passive"))
      (node (ref "P4") (pin "2") (pinfunction "2_2") (pintype "passive"))
      (node (ref "Q2") (pin "1") (pinfunction "VSS_1") (pintype "passive"))
      (node (ref "Q3") (pin "E") (pinfunction "E_E") (pintype "passive"))
      (node (ref "Q4") (pin "E") (pinfunction "E_E") (pintype "passive"))
      (node (ref "R11") (pin "2") (pinfunction "2_2") (pintype "passive"))
      (node (ref "R14") (pin "3") (pinfunction "3_3") (pintype "passive"))
      (node (ref "R15") (pin "1") (pinfunction "1_1") (pintype "passive"))
      (node (ref "R19") (pin "1") (pinfunction "1_1") (pintype "passive"))
      (node (ref "R20") (pin "1") (pinfunction "1_1") (pintype "passive"))
      (node (ref "R22") (pin "1") (pinfunction "1_1") (pintype "passive"))
      (node (ref "R29") (pin "2") (pinfunction "2_2") (pintype "passive"))
      (node (ref "R31") (pin "1") (pinfunction "1_1") (pintype "passive"))
      (node (ref "R35") (pin "1") (pinfunction "1_1") (pintype "passive"))
      (node (ref "R7") (pin "2") (pinfunction "2_2") (pintype "passive"))
      (node (ref "SW1") (pin "1") (pinfunction "1_1") (pintype "passive"))
      (node (ref "U1") (pin "1") (pinfunction "TEMP_1") (pintype "passive"))
      (node (ref "U1") (pin "3") (pinfunction "GND_3") (pintype "passive"))
      (node (ref "U2") (pin "2") (pinfunction "GND_2") (pintype "power_in"))
      (node (ref "U3") (pin "2") (pinfunction "GND_2") (pintype "passive"))
      (node (ref "U4") (pin "23") (pinfunction "VSS_1_23") (pintype "passive"))
      (node (ref "U4") (pin "35") (pinfunction "VSS_2_35") (pintype "passive"))
      (node (ref "U4") (pin "47") (pinfunction "VSS_3_47") (pintype "passive"))
      (node (ref "U4") (pin "8") (pinfunction "VSSA_8") (pintype "passive"))
      (node (ref "U6") (pin "3") (pinfunction "GND_3") (pintype "passive"))
      (node (ref "U6") (pin "4") (pinfunction "GND_4") (pintype "passive"))
      (node (ref "USB1") (pin "4") (pinfunction "ID_4") (pintype "passive"))
      (node (ref "USB1") (pin "5") (pinfunction "-_5") (pintype "passive"))
    )
    (net (code "43") (name "Net-(B1-Pad2)") (class "Default")
      (node (ref "B1") (pin "2") (pinfunction "2_2") (pintype "passive"))
      (node (ref "Q3") (pin "C") (pinfunction "C_C") (pintype "passive"))
    )
    (net (code "44") (name "Net-(C13-Pad1)") (class "Default")
      (node (ref "C13") (pin "1") (pinfunction "1_1") (pintype "passive"))
      (node (ref "C14") (pin "1") (pinfunction "1_1") (pintype "passive"))
      (node (ref "D5") (pin "K") (pinfunction "K_K") (pintype "passive"))
      (node (ref "Q1") (pin "S") (pinfunction "S_S") (pintype "passive"))
      (node (ref "SW2") (pin "2") (pinfunction "COM2_2") (pintype "passive"))
    )
    (net (code "45") (name "Net-(D1-PadK)") (class "Default")
      (node (ref "D1") (pin "K") (pinfunction "K_K") (pintype "passive"))
      (node (ref "R7") (pin "1") (pinfunction "1_1") (pintype "passive"))
    )
    (net (code "46") (name "Net-(D2-PadA)") (class "Default")
      (node (ref "D2") (pin "A") (pinfunction "A_A") (pintype "passive"))
      (node (ref "R2") (pin "2") (pinfunction "2_2") (pintype "passive"))
    )
    (net (code "47") (name "Net-(D3-PadA)") (class "Default")
      (node (ref "D3") (pin "A") (pinfunction "A_A") (pintype "passive"))
      (node (ref "R3") (pin "2") (pinfunction "2_2") (pintype "passive"))
    )
    (net (code "48") (name "Net-(D4-PadK)") (class "Default")
      (node (ref "D4") (pin "K") (pinfunction "K_K") (pintype "passive"))
      (node (ref "R10") (pin "1") (pinfunction "1_1") (pintype "passive"))
    )
    (net (code "49") (name "Net-(D8-PadA)") (class "Default")
      (node (ref "D8") (pin "A") (pinfunction "A_A") (pintype "passive"))
      (node (ref "JK1") (pin "1") (pinfunction "1_1") (pintype "passive"))
      (node (ref "Q4") (pin "C") (pinfunction "C_C") (pintype "passive"))
    )
    (net (code "50") (name "Net-(D9-PadA)") (class "Default")
      (node (ref "D9") (pin "A") (pinfunction "A_A") (pintype "passive"))
      (node (ref "R33") (pin "1") (pinfunction "1_1") (pintype "passive"))
    )
    (net (code "51") (name "Net-(J2-C1N)") (class "Default")
      (node (ref "C8") (pin "1") (pinfunction "1_1") (pintype "passive"))
      (node (ref "J2") (pin "5") (pinfunction "C1N_5") (pintype "passive"))
    )
    (net (code "52") (name "Net-(J2-C1P)") (class "Default")
      (node (ref "C8") (pin "2") (pinfunction "2_2") (pintype "passive"))
      (node (ref "J2") (pin "4") (pinfunction "C1P_4") (pintype "passive"))
    )
    (net (code "53") (name "Net-(J2-C2N)") (class "Default")
      (node (ref "C5") (pin "1") (pinfunction "1_1") (pintype "passive"))
      (node (ref "J2") (pin "3") (pinfunction "C2N_3") (pintype "passive"))
    )
    (net (code "54") (name "Net-(J2-C2P)") (class "Default")
      (node (ref "C5") (pin "2") (pinfunction "2_2") (pintype "passive"))
      (node (ref "J2") (pin "2") (pinfunction "C2P_2") (pintype "passive"))
    )
    (net (code "55") (name "Net-(J2-DC)") (class "Default")
      (node (ref "J2") (pin "15") (pinfunction "DC_15") (pintype "passive"))
      (node (ref "R14") (pin "2") (pinfunction "2_2") (pintype "passive"))
    )
    (net (code "56") (name "Net-(J2-IREF)") (class "Default")
      (node (ref "J2") (pin "26") (pinfunction "IREF_26") (pintype "passive"))
      (node (ref "R20") (pin "2") (pinfunction "2_2") (pintype "passive"))
    )
    (net (code "57") (name "Net-(J2-RES)") (class "Default")
      (node (ref "C15") (pin "1") (pinfunction "1_1") (pintype "passive"))
      (node (ref "D6") (pin "A") (pinfunction "A_A") (pintype "passive"))
      (node (ref "J2") (pin "14") (pinfunction "RES_14") (pintype "passive"))
      (node (ref "R12") (pin "1") (pinfunction "1_1") (pintype "passive"))
    )
    (net (code "58") (name "Net-(J2-VCC)") (class "Default")
      (node (ref "C18") (pin "2") (pinfunction "2_2") (pintype "passive"))
      (node (ref "J2") (pin "28") (pinfunction "VCC_28") (pintype "passive"))
    )
    (net (code "59") (name "Net-(J2-VCCMH)") (class "Default")
      (node (ref "C16") (pin "2") (pinfunction "2_2") (pintype "passive"))
      (node (ref "J2") (pin "27") (pinfunction "VCCMH_27") (pintype "passive"))
    )
    (net (code "60") (name "Net-(J5-Pad1)") (class "Default")
      (node (ref "J5") (pin "1") (pinfunction "1_1") (pintype "passive"))
      (node (ref "L2") (pin "1") (pinfunction "1_1") (pintype "passive"))
    )
    (net (code "61") (name "Net-(L2-Pad2)") (class "Default")
      (node (ref "L2") (pin "2") (pinfunction "2_2") (pintype "passive"))
      (node (ref "L3") (pin "1") (pinfunction "1_1") (pintype "passive"))
    )
    (net (code "62") (name "Net-(M1-EN)") (class "Default")
      (node (ref "M1") (pin "3") (pinfunction "EN_3") (pintype "passive"))
      (node (ref "R6") (pin "2") (pinfunction "2_2") (pintype "passive"))
    )
    (net (code "63") (name "Net-(M1-RST)") (class "Default")
      (node (ref "M1") (pin "1") (pinfunction "RST_1") (pintype "passive"))
      (node (ref "R4") (pin "2") (pinfunction "2_2") (pintype "passive"))
    )
    (net (code "64") (name "Net-(P1-Pad3)") (class "Default")
      (node (ref "P1") (pin "3") (pinfunction "3_3") (pintype "passive"))
      (node (ref "R8") (pin "2") (pinfunction "2_2") (pintype "passive"))
    )
    (net (code "65") (name "Net-(P1-Pad4)") (class "Default")
      (node (ref "P1") (pin "4") (pinfunction "4_4") (pintype "passive"))
      (node (ref "R9") (pin "1") (pinfunction "1_1") (pintype "passive"))
    )
    (net (code "66") (name "Net-(Q1-PadG)") (class "Default")
      (node (ref "Q1") (pin "G") (pinfunction "G_G") (pintype "passive"))
      (node (ref "R13") (pin "1") (pinfunction "1_1") (pintype "passive"))
    )
    (net (code "67") (name "Net-(Q3-PadB)") (class "Default")
      (node (ref "Q3") (pin "B") (pinfunction "B_B") (pintype "passive"))
      (node (ref "R26") (pin "1") (pinfunction "1_1") (pintype "passive"))
    )
    (net (code "68") (name "Net-(Q4-PadB)") (class "Default")
      (node (ref "Q4") (pin "B") (pinfunction "B_B") (pintype "passive"))
      (node (ref "R34") (pin "1") (pinfunction "1_1") (pintype "passive"))
      (node (ref "R35") (pin "2") (pinfunction "2_2") (pintype "passive"))
    )
    (net (code "69") (name "Net-(R30-Pad1)") (class "Default")
      (node (ref "R30") (pin "1") (pinfunction "1_1") (pintype "passive"))
      (node (ref "R32") (pin "1") (pinfunction "1_1") (pintype "passive"))
      (node (ref "U6") (pin "2") (pinfunction "R_2") (pintype "passive"))
    )
    (net (code "70") (name "Net-(R30-Pad2)") (class "Default")
      (node (ref "R30") (pin "2") (pinfunction "2_2") (pintype "passive"))
      (node (ref "U6") (pin "1") (pinfunction "R_1") (pintype "passive"))
    )
    (net (code "71") (name "Net-(SW2-NO2)") (class "Default")
      (node (ref "C21") (pin "2") (pinfunction "2_2") (pintype "passive"))
      (node (ref "C22") (pin "2") (pinfunction "2_2") (pintype "passive"))
      (node (ref "L1") (pin "1") (pinfunction "1_1") (pintype "passive"))
      (node (ref "SW2") (pin "4") (pinfunction "NO2_4") (pintype "passive"))
      (node (ref "U3") (pin "4") (pinfunction "EN_4") (pintype "passive"))
      (node (ref "U3") (pin "5") (pinfunction "VCC_5") (pintype "passive"))
    )
    (net (code "72") (name "Net-(U1-CE)") (class "Default")
      (node (ref "C1") (pin "2") (pinfunction "2_2") (pintype "passive"))
      (node (ref "R1") (pin "2") (pinfunction "2_2") (pintype "passive"))
      (node (ref "R2") (pin "1") (pinfunction "1_1") (pintype "passive"))
      (node (ref "R3") (pin "1") (pinfunction "1_1") (pintype "passive"))
      (node (ref "U1") (pin "4") (pinfunction "VCC_4") (pintype "passive"))
      (node (ref "U1") (pin "8") (pinfunction "CE_8") (pintype "passive"))
    )
    (net (code "73") (name "Net-(U1-PROG)") (class "Default")
      (node (ref "R11") (pin "1") (pinfunction "1_1") (pintype "passive"))
      (node (ref "U1") (pin "2") (pinfunction "PROG_2") (pintype "passive"))
    )
    (net (code "74") (name "Net-(U1-~{CHRG})") (class "Default")
      (node (ref "D3") (pin "K") (pinfunction "K_K") (pintype "passive"))
      (node (ref "U1") (pin "7") (pinfunction "~{CHRG}_7") (pintype "passive"))
    )
    (net (code "75") (name "Net-(U1-~{STDBY})") (class "Default")
      (node (ref "D2") (pin "K") (pinfunction "K_K") (pintype "passive"))
      (node (ref "U1") (pin "6") (pinfunction "~{STDBY}_6") (pintype "passive"))
    )
    (net (code "76") (name "Net-(U2-BP)") (class "Default")
      (node (ref "C10") (pin "2") (pinfunction "2_2") (pintype "passive"))
      (node (ref "U2") (pin "4") (pinfunction "BP_4") (pintype "passive"))
    )
    (net (code "77") (name "Net-(U3-FB)") (class "Default")
      (node (ref "R21") (pin "1") (pinfunction "1_1") (pintype "passive"))
      (node (ref "R22") (pin "2") (pinfunction "2_2") (pintype "passive"))
      (node (ref "U3") (pin "3") (pinfunction "FB_3") (pintype "passive"))
    )
    (net (code "78") (name "Net-(U3-LX)") (class "Default")
      (node (ref "D7") (pin "A") (pinfunction "A_A") (pintype "passive"))
      (node (ref "L1") (pin "2") (pinfunction "2_2") (pintype "passive"))
      (node (ref "U3") (pin "1") (pinfunction "LX_1") (pintype "passive"))
    )
    (net (code "79") (name "Net-(U3-OC)") (class "Default")
      (node (ref "R19") (pin "2") (pinfunction "2_2") (pintype "passive"))
      (node (ref "U3") (pin "6") (pinfunction "OC_6") (pintype "passive"))
    )
    (net (code "80") (name "Net-(U5-Con)") (class "Default")
      (node (ref "C31") (pin "1") (pinfunction "1_1") (pintype "passive"))
      (node (ref "R31") (pin "2") (pinfunction "2_2") (pintype "passive"))
      (node (ref "U5") (pin "Hole") (pinfunction "Con_Hole") (pintype "passive"))
      (node (ref "U6") (pin "8") (pinfunction "N/F_8") (pintype "passive"))
    )
    (net (code "81") (name "Net-(U6-LED)") (class "Default")
      (node (ref "R33") (pin "2") (pinfunction "2_2") (pintype "passive"))
      (node (ref "U6") (pin "6") (pinfunction "LED_6") (pintype "passive"))
    )
    (net (code "82") (name "Net-(U6-VDD)") (class "Default")
      (node (ref "C32") (pin "2") (pinfunction "2_2") (pintype "passive"))
      (node (ref "C33") (pin "2") (pinfunction "2_2") (pintype "passive"))
      (node (ref "J5") (pin "2") (pinfunction "2_2") (pintype "passive"))
      (node (ref "JK1") (pin "4") (pinfunction "4_4") (pintype "passive"))
      (node (ref "L3") (pin "3") (pinfunction "3_3") (pintype "passive"))
      (node (ref "R32") (pin "2") (pinfunction "2_2") (pintype "passive"))
      (node (ref "U6") (pin "7") (pinfunction "VDD_7") (pintype "passive"))
    )
    (net (code "83") (name "Net-(U6-VIN)") (class "Default")
      (node (ref "C33") (pin "1") (pinfunction "1_1") (pintype "passive"))
      (node (ref "L3") (pin "2") (pinfunction "2_2") (pintype "passive"))
      (node (ref "U6") (pin "5") (pinfunction "VIN_5") (pintype "passive"))
    )
    (net (code "84") (name "Net-(USB1-D+)") (class "Default")
      (node (ref "R25") (pin "1") (pinfunction "1_1") (pintype "passive"))
      (node (ref "USB1") (pin "3") (pinfunction "D+_3") (pintype "passive"))
    )
    (net (code "85") (name "Net-(USB1-D-)") (class "Default")
      (node (ref "R24") (pin "1") (pinfunction "1_1") (pintype "passive"))
      (node (ref "USB1") (pin "2") (pinfunction "D-_2") (pintype "passive"))
    )
    (net (code "86") (name "VBAT3.7") (class "Default")
      (node (ref "C3") (pin "1") (pinfunction "1_1") (pintype "passive"))
      (node (ref "J1") (pin "1") (pinfunction "1_1") (pintype "passive"))
      (node (ref "SW2") (pin "5") (pinfunction "COM2_5") (pintype "passive"))
      (node (ref "U1") (pin "5") (pinfunction "BAT_5") (pintype "passive"))
    )
    (net (code "87") (name "VBUS") (class "Default")
      (node (ref "D5") (pin "A") (pinfunction "A_A") (pintype "passive"))
      (node (ref "R1") (pin "1") (pinfunction "1_1") (pintype "passive"))
      (node (ref "R13") (pin "2") (pinfunction "2_2") (pintype "passive"))
      (node (ref "R15") (pin "2") (pinfunction "2_2") (pintype "passive"))
      (node (ref "USB1") (pin "1") (pinfunction "+_1") (pintype "passive"))
    )
    (net (code "88") (name "VCC3V3") (class "Default")
      (node (ref "B1") (pin "1") (pinfunction "1_1") (pintype "passive"))
      (node (ref "C17") (pin "1") (pinfunction "1_1") (pintype "passive"))
      (node (ref "C25") (pin "2") (pinfunction "2_2") (pintype "passive"))
      (node (ref "C26") (pin "2") (pinfunction "2_2") (pintype "passive"))
      (node (ref "C27") (pin "2") (pinfunction "2_2") (pintype "passive"))
      (node (ref "C28") (pin "2") (pinfunction "2_2") (pintype "passive"))
      (node (ref "C4") (pin "2") (pinfunction "2_2") (pintype "passive"))
      (node (ref "C6") (pin "2") (pinfunction "2_2") (pintype "passive"))
      (node (ref "C7") (pin "2") (pinfunction "2_2") (pintype "passive"))
      (node (ref "D1") (pin "A") (pinfunction "A_A") (pintype "passive"))
      (node (ref "D4") (pin "A") (pinfunction "A_A") (pintype "passive"))
      (node (ref "J3") (pin "2") (pinfunction "2_2") (pintype "passive"))
      (node (ref "J4") (pin "5") (pinfunction "5_5") (pintype "passive"))
      (node (ref "M1") (pin "8") (pinfunction "VCC_8") (pintype "passive"))
      (node (ref "P1") (pin "1") (pinfunction "1_1") (pintype "passive"))
      (node (ref "P1") (pin "2") (pinfunction "2_2") (pintype "passive"))
      (node (ref "P2") (pin "4") (pinfunction "4_4") (pintype "passive"))
      (node (ref "P3") (pin "18") (pinfunction "18_18") (pintype "passive"))
      (node (ref "P4") (pin "1") (pinfunction "1_1") (pintype "passive"))
      (node (ref "Q2") (pin "3") (pinfunction "VIN_3") (pintype "passive"))
      (node (ref "R16") (pin "2") (pinfunction "2_2") (pintype "passive"))
      (node (ref "R23") (pin "1") (pinfunction "1_1") (pintype "passive"))
      (node (ref "R4") (pin "1") (pinfunction "1_1") (pintype "passive"))
      (node (ref "R5") (pin "1") (pinfunction "1_1") (pintype "passive"))
      (node (ref "R6") (pin "1") (pinfunction "1_1") (pintype "passive"))
      (node (ref "U2") (pin "5") (pinfunction "VOUT_5") (pintype "power_in"))
      (node (ref "U4") (pin "24") (pinfunction "VDD_1_24") (pintype "passive"))
      (node (ref "U4") (pin "36") (pinfunction "VDD_2_36") (pintype "passive"))
      (node (ref "U4") (pin "48") (pinfunction "VDD_3_48") (pintype "passive"))
      (node (ref "U4") (pin "9") (pinfunction "VDDA_9") (pintype "passive"))
    )
    (net (code "89") (name "VCC5V") (class "Default")
      (node (ref "C9") (pin "2") (pinfunction "2_2") (pintype "passive"))
      (node (ref "D8") (pin "K") (pinfunction "K_K") (pintype "passive"))
      (node (ref "J6") (pin "4") (pinfunction "4_4") (pintype "passive"))
      (node (ref "JK1") (pin "2") (pinfunction "2_2") (pintype "passive"))
      (node (ref "JK1") (pin "3") (pinfunction "3_3") (pintype "passive"))
      (node (ref "P4") (pin "3") (pinfunction "3_3") (pintype "passive"))
      (node (ref "R27") (pin "1") (pinfunction "1_1") (pintype "passive"))
      (node (ref "SW2") (pin "3") (pinfunction "NO1_3") (pintype "passive"))
      (node (ref "U2") (pin "1") (pinfunction "VIN_1") (pintype "power_in"))
      (node (ref "U2") (pin "3") (pinfunction "EN_3") (pintype "input"))
    )
    (net (code "90") (name "VCC_OLED") (class "Default")
      (node (ref "C11") (pin "1") (pinfunction "1_1") (pintype "passive"))
      (node (ref "C12") (pin "1") (pinfunction "1_1") (pintype "passive"))
      (node (ref "D6") (pin "K") (pinfunction "K_K") (pintype "passive"))
      (node (ref "J2") (pin "11") (pinfunction "BS1_11") (pintype "passive"))
      (node (ref "J2") (pin "6") (pinfunction "VBAT_6") (pintype "passive"))
      (node (ref "J2") (pin "9") (pinfunction "VDD_9") (pintype "passive"))
      (node (ref "Q2") (pin "2") (pinfunction "VOUT_2") (pintype "passive"))
      (node (ref "R12") (pin "2") (pinfunction "2_2") (pintype "passive"))
      (node (ref "R14") (pin "1") (pinfunction "1_1") (pintype "passive"))
      (node (ref "R16") (pin "1") (pinfunction "1_1") (pintype "passive"))
      (node (ref "R17") (pin "1") (pinfunction "1_1") (pintype "passive"))
      (node (ref "R18") (pin "1") (pinfunction "1_1") (pintype "passive"))
    )
    (net (code "91") (name "unconnected-(J2-NC-Pad7)") (class "Default")
      (node (ref "J2") (pin "7") (pinfunction "NC_7") (pintype "passive+no_connect"))
    )
    (net (code "92") (name "unconnected-(J6-Pad5)") (class "Default")
      (node (ref "J6") (pin "5") (pinfunction "5_5") (pintype "passive+no_connect"))
    )
    (net (code "93") (name "unconnected-(M1-ADC-Pad2)") (class "Default")
      (node (ref "M1") (pin "2") (pinfunction "ADC_2") (pintype "passive"))
    )
    (net (code "94") (name "unconnected-(M1-CS0-Pad9)") (class "Default")
      (node (ref "M1") (pin "9") (pinfunction "CS0_9") (pintype "passive"))
    )
    (net (code "95") (name "unconnected-(M1-GPIO0-Pad18)") (class "Default")
      (node (ref "M1") (pin "18") (pinfunction "GPIO0_18") (pintype "passive"))
    )
    (net (code "96") (name "unconnected-(M1-GPIO2-Pad17)") (class "Default")
      (node (ref "M1") (pin "17") (pinfunction "GPIO2_17") (pintype "passive"))
    )
    (net (code "97") (name "unconnected-(M1-GPIO9-Pad11)") (class "Default")
      (node (ref "M1") (pin "11") (pinfunction "GPIO9_11") (pintype "passive"))
    )
    (net (code "98") (name "unconnected-(M1-GPIO10-Pad12)") (class "Default")
      (node (ref "M1") (pin "12") (pinfunction "GPIO10_12") (pintype "passive"))
    )
    (net (code "99") (name "unconnected-(M1-GPIO12-Pad6)") (class "Default")
      (node (ref "M1") (pin "6") (pinfunction "GPIO12_6") (pintype "passive"))
    )
    (net (code "100") (name "unconnected-(M1-GPIO13-Pad7)") (class "Default")
      (node (ref "M1") (pin "7") (pinfunction "GPIO13_7") (pintype "passive"))
    )
    (net (code "101") (name "unconnected-(M1-GPIO14-Pad5)") (class "Default")
      (node (ref "M1") (pin "5") (pinfunction "GPIO14_5") (pintype "passive"))
    )
    (net (code "102") (name "unconnected-(M1-GPIO16-Pad4)") (class "Default")
      (node (ref "M1") (pin "4") (pinfunction "GPIO16_4") (pintype "passive"))
    )
    (net (code "103") (name "unconnected-(M1-MISO-Pad10)") (class "Default")
      (node (ref "M1") (pin "10") (pinfunction "MISO_10") (pintype "passive"))
    )
    (net (code "104") (name "unconnected-(M1-MOSI-Pad13)") (class "Default")
      (node (ref "M1") (pin "13") (pinfunction "MOSI_13") (pintype "passive"))
    )
    (net (code "105") (name "unconnected-(M1-RXD0-Pad21)") (class "Default")
      (node (ref "M1") (pin "21") (pinfunction "RXD0_21") (pintype "passive"))
    )
    (net (code "106") (name "unconnected-(M1-SCLK-Pad14)") (class "Default")
      (node (ref "M1") (pin "14") (pinfunction "SCLK_14") (pintype "passive"))
    )
    (net (code "107") (name "unconnected-(M1-TXD0-Pad22)") (class "Default")
      (node (ref "M1") (pin "22") (pinfunction "TXD0_22") (pintype "passive"))
    )
    (net (code "108") (name "unconnected-(SW2-NC1-Pad1)") (class "Default")
      (node (ref "SW2") (pin "1") (pinfunction "NC1_1") (pintype "passive"))
    )
    (net (code "109") (name "unconnected-(SW2-NC2-Pad6)") (class "Default")
      (node (ref "SW2") (pin "6") (pinfunction "NC2_6") (pintype "passive"))
    )
  )
)
